# INTERFACE.net
KiCad netlist of a schematic drawn in Altium Designer
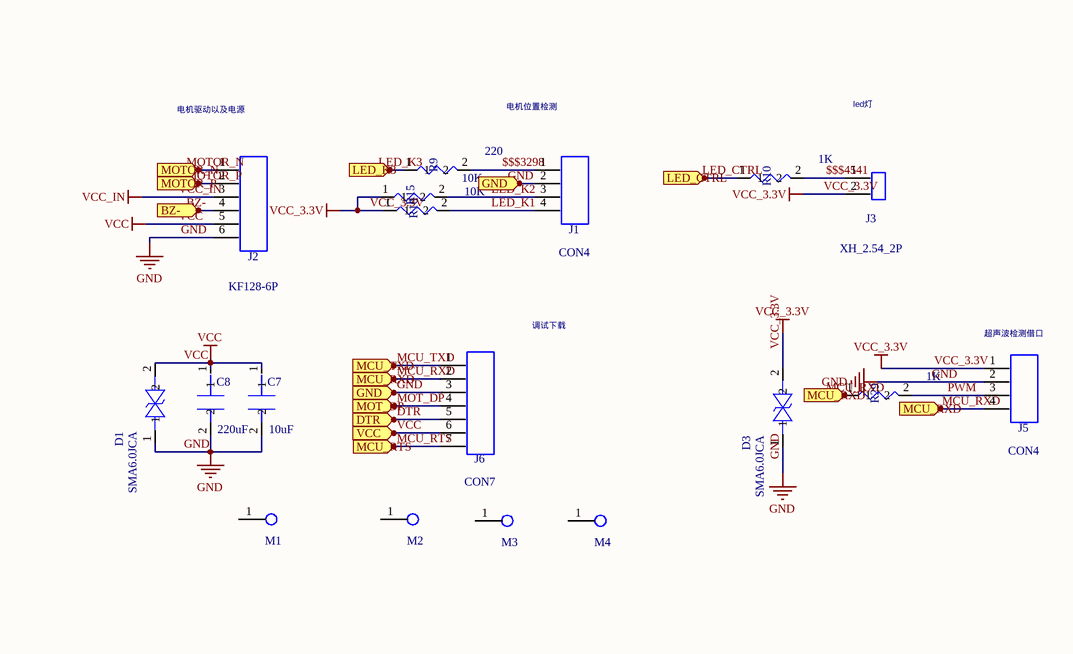
[diagram p0: INTERFACE.SchDoc, top left]
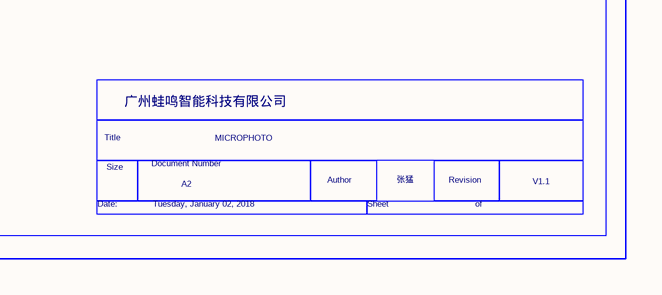
[diagram p1: INTERFACE.SchDoc, bottom right]

(export (version "E")
  (design (tool "Eeschema 10.0.6"))
  (components
    (comp (ref "C7")
      (value "10uF")
      (fields (field (name "Comment") "CAP"))
      (libsource (lib "*") (part "CAP"))
    )
    (comp (ref "C8")
      (value "220uF")
      (fields (field (name "Comment") "CAP"))
      (libsource (lib "*") (part "CAP"))
    )
    (comp (ref "D1")
      (value "SMA6.0JCA")
      (fields (field (name "Comment") "DIODE_BI_DIR_TRIG") (field (name "CREATED_BY") "JJJ"))
      (libsource (lib "*") (part "DIODE_BI_DIR_TRIG"))
    )
    (comp (ref "D3")
      (value "SMA6.0JCA")
      (fields (field (name "Comment") "DIODE_BI_DIR_TRIG") (field (name "CREATED_BY") "JJJ"))
      (libsource (lib "*") (part "DIODE_BI_DIR_TRIG"))
    )
    (comp (ref "J1") (value "CON4") (libsource (lib "*") (part "CON4")))
    (comp (ref "J2") (value "KF128-6P") (libsource (lib "*") (part "KF128-6P")))
    (comp (ref "J3") (value "XH_2.54_2P") (libsource (lib "*") (part "XH_2.54_2P")))
    (comp (ref "J5") (value "CON4") (libsource (lib "*") (part "CON4")))
    (comp (ref "J6") (value "CON7") (libsource (lib "*") (part "CON7")))
    (comp (ref "M1") (value "M2") (libsource (lib "*") (part "M2")))
    (comp (ref "M2") (value "M2") (libsource (lib "*") (part "M2")))
    (comp (ref "M3") (value "M2") (libsource (lib "*") (part "M2")))
    (comp (ref "M4") (value "M2") (libsource (lib "*") (part "M2")))
    (comp (ref "R9")
      (value "220")
      (description "RES,thick film,47KOhm,+/-5%,1/16W,SMD0402")
      (fields (field (name "Comment") "RESISTOR"))
      (libsource (lib "*") (part "RESISTOR"))
    )
    (comp (ref "R10")
      (value "1K")
      (description "RES,thick film,47KOhm,+/-5%,1/16W,SMD0402")
      (fields (field (name "Comment") "RESISTOR"))
      (libsource (lib "*") (part "RESISTOR"))
    )
    (comp (ref "R15")
      (value "10K")
      (description "RES,thick film,47KOhm,+/-5%,1/16W,SMD0402")
      (fields (field (name "Comment") "RESISTOR"))
      (libsource (lib "*") (part "RESISTOR"))
    )
    (comp (ref "R16")
      (value "10K")
      (description "RES,thick film,47KOhm,+/-5%,1/16W,SMD0402")
      (fields (field (name "Comment") "RESISTOR"))
      (libsource (lib "*") (part "RESISTOR"))
    )
    (comp (ref "R29")
      (value "1K")
      (description "RES,thick film,47KOhm,+/-5%,1/16W,SMD0402")
      (fields (field (name "Comment") "RESISTOR"))
      (libsource (lib "*") (part "RESISTOR"))
    )
  )
  (nets
    (net (code "1") (name "/$$$3298") (class "Default")
      (node (ref "J1") (pin "1") (pintype "passive"))
      (node (ref "R9") (pin "2") (pinfunction "2_2") (pintype "passive"))
    )
    (net (code "2") (name "/$$$4541") (class "Default")
      (node (ref "J3") (pin "1") (pintype "passive"))
      (node (ref "R10") (pin "2") (pinfunction "2_2") (pintype "passive"))
    )
    (net (code "3") (name "/BZ-") (class "Default") (node (ref "J2") (pin "4") (pintype "passive")))
    (net (code "4") (name "/DTR") (class "Default") (node (ref "J6") (pin "5") (pintype "passive")))
    (net (code "5") (name "/LED_CTRL") (class "Default")
      (node (ref "R10") (pin "1") (pinfunction "1_1") (pintype "passive"))
    )
    (net (code "6") (name "/LED_K1") (class "Default")
      (node (ref "J1") (pin "4") (pintype "passive"))
      (node (ref "R16") (pin "2") (pinfunction "2_2") (pintype "passive"))
    )
    (net (code "7") (name "/LED_K2") (class "Default")
      (node (ref "J1") (pin "3") (pintype "passive"))
      (node (ref "R15") (pin "2") (pinfunction "2_2") (pintype "passive"))
    )
    (net (code "8") (name "/LED_K3") (class "Default")
      (node (ref "R9") (pin "1") (pinfunction "1_1") (pintype "passive"))
    )
    (net (code "9") (name "/MCU_RTS") (class "Default") (node (ref "J6") (pin "7") (pintype "passive")))
    (net (code "10") (name "/MCU_RXD") (class "Default")
      (node (ref "J5") (pin "4") (pintype "passive"))
      (node (ref "J6") (pin "2") (pintype "passive"))
      (node (ref "R29") (pin "1") (pinfunction "1_1") (pintype "passive"))
    )
    (net (code "11") (name "/MCU_TXD") (class "Default") (node (ref "J6") (pin "1") (pintype "passive")))
    (net (code "12") (name "/MOTOR_N") (class "Default") (node (ref "J2") (pin "1") (pintype "passive")))
    (net (code "13") (name "/MOTOR_P") (class "Default") (node (ref "J2") (pin "2") (pintype "passive")))
    (net (code "14") (name "/MOT_DP") (class "Default") (node (ref "J6") (pin "4") (pintype "passive")))
    (net (code "15") (name "/PWM") (class "Default")
      (node (ref "J5") (pin "3") (pintype "passive"))
      (node (ref "R29") (pin "2") (pinfunction "2_2") (pintype "passive"))
    )
    (net (code "16") (name "GND") (class "Default")
      (node (ref "C7") (pin "2") (pinfunction "2_2") (pintype "passive"))
      (node (ref "C8") (pin "2") (pinfunction "2_2") (pintype "passive"))
      (node (ref "D1") (pin "1") (pinfunction "1_1") (pintype "passive"))
      (node (ref "D3") (pin "1") (pinfunction "1_1") (pintype "passive"))
      (node (ref "J1") (pin "2") (pintype "passive"))
      (node (ref "J2") (pin "6") (pintype "passive"))
      (node (ref "J5") (pin "2") (pintype "passive"))
      (node (ref "J6") (pin "3") (pintype "passive"))
    )
    (net (code "17") (name "VCC") (class "Default")
      (node (ref "C7") (pin "1") (pinfunction "1_1") (pintype "passive"))
      (node (ref "C8") (pin "1") (pinfunction "1_1") (pintype "passive"))
      (node (ref "D1") (pin "2") (pinfunction "2_2") (pintype "passive"))
      (node (ref "J2") (pin "5") (pintype "passive"))
      (node (ref "J6") (pin "6") (pintype "passive"))
    )
    (net (code "18") (name "VCC_3.3V") (class "Default")
      (node (ref "D3") (pin "2") (pinfunction "2_2") (pintype "passive"))
      (node (ref "J3") (pin "2") (pintype "passive"))
      (node (ref "J5") (pin "1") (pintype "passive"))
      (node (ref "R15") (pin "1") (pinfunction "1_1") (pintype "passive"))
      (node (ref "R16") (pin "1") (pinfunction "1_1") (pintype "passive"))
    )
    (net (code "19") (name "VCC_IN") (class "Default") (node (ref "J2") (pin "3") (pintype "passive")))
    (net (code "20") (name "unconnected-(M1-Pad1)") (class "Default")
      (node (ref "M1") (pin "1") (pintype "passive"))
    )
    (net (code "21") (name "unconnected-(M2-Pad1)") (class "Default")
      (node (ref "M2") (pin "1") (pintype "passive"))
    )
    (net (code "22") (name "unconnected-(M3-Pad1)") (class "Default")
      (node (ref "M3") (pin "1") (pintype "passive"))
    )
    (net (code "23") (name "unconnected-(M4-Pad1)") (class "Default")
      (node (ref "M4") (pin "1") (pintype "passive"))
    )
  )
)
